# PCB_DYBoard_Transducer_CAN_ADS1113_V1.net
KiCad netlist of a schematic drawn in Altium Designer
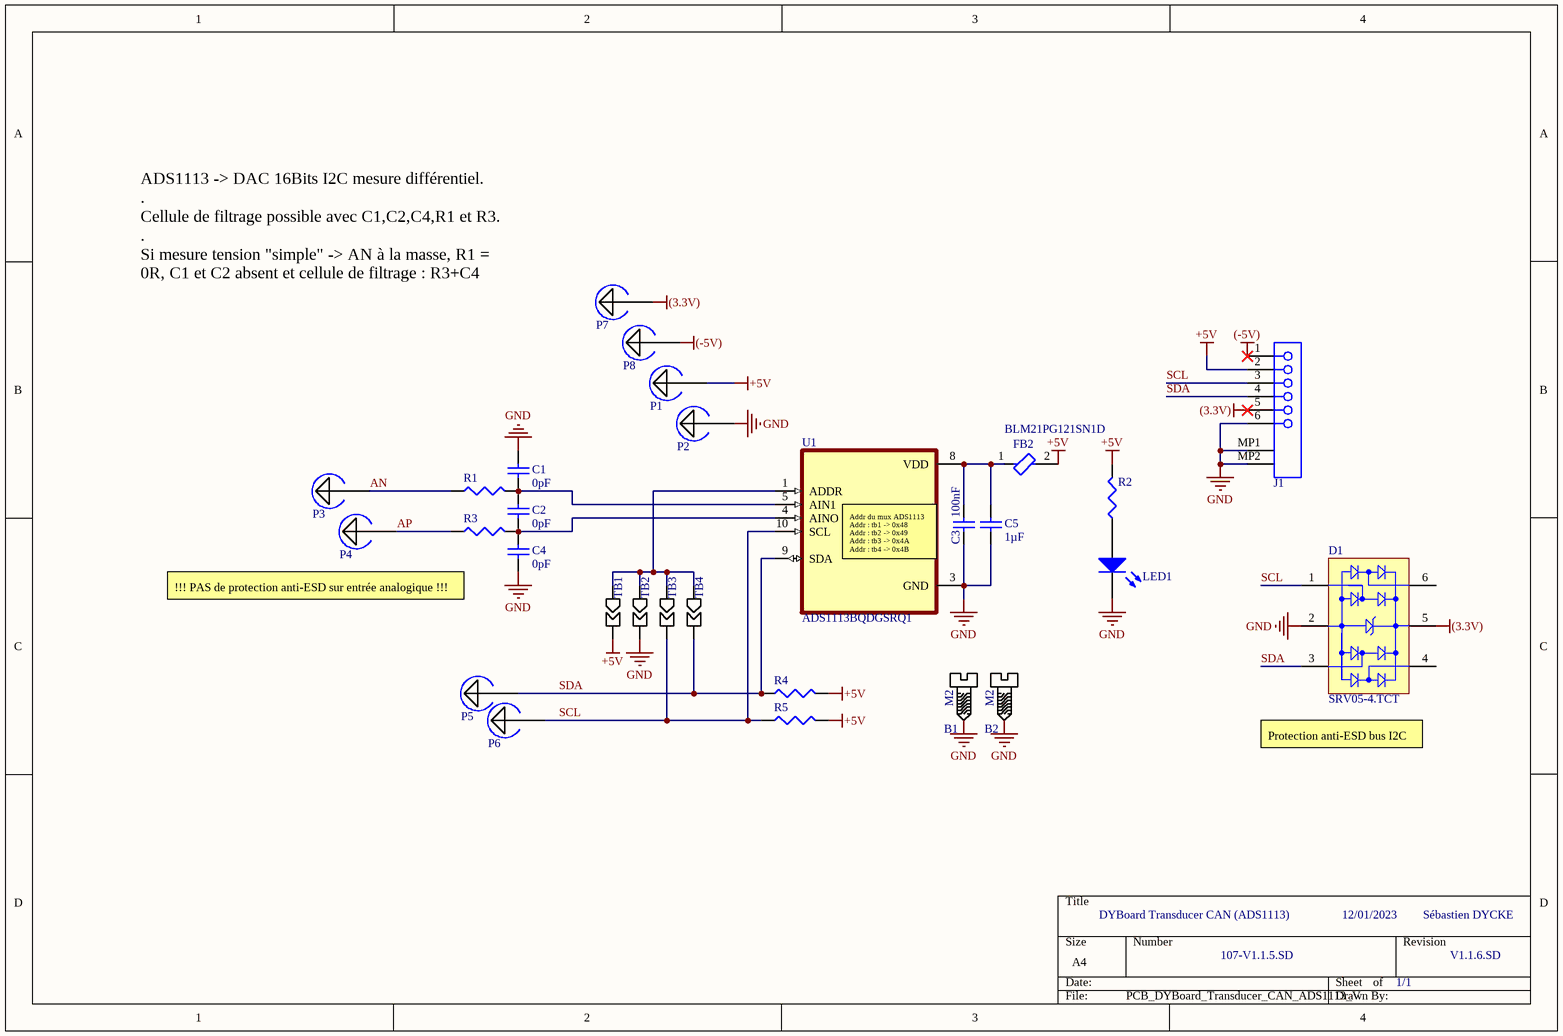
[diagram p0: PCB_DYBoard_Transducer_CAN_ADS1113_V1.SchDoc]

(export (version "E")
  (design (tool "Eeschema 10.0.6"))
  (components
    (comp (ref "B1")
      (value "bolt_M2")
      (footprint "bolt_M2")
      (libsource (lib "Lib_Altium_Sebastien_DYCKE") (part "bolt_M2"))
    )
    (comp (ref "B2")
      (value "bolt_M2")
      (footprint "bolt_M2")
      (libsource (lib "Lib_Altium_Sebastien_DYCKE") (part "bolt_M2"))
    )
    (comp (ref "C1")
      (value "0pF")
      (footprint "1608[0603]")
      (description "Capacitor (Semiconductor SIM Model)")
      (fields (field (name "Comment") "Cap Semi") (field (name "PUBLISHER") "Altium Limited"))
      (libsource (lib "Miscellaneous Devices") (part "Cap Semi"))
    )
    (comp (ref "C2")
      (value "0pF")
      (footprint "1608[0603]")
      (description "Capacitor (Semiconductor SIM Model)")
      (fields (field (name "Comment") "Cap Semi") (field (name "PUBLISHER") "Altium Limited"))
      (libsource (lib "Miscellaneous Devices") (part "Cap Semi"))
    )
    (comp (ref "C3")
      (value "100nF")
      (footprint "1608[0603]")
      (description "Capacitor (Semiconductor SIM Model)")
      (fields (field (name "Comment") "Cap Semi") (field (name "PUBLISHER") "Altium Limited"))
      (libsource (lib "Miscellaneous Devices") (part "Cap Semi"))
    )
    (comp (ref "C4")
      (value "0pF")
      (footprint "1608[0603]")
      (description "Capacitor (Semiconductor SIM Model)")
      (fields (field (name "Comment") "Cap Semi") (field (name "PUBLISHER") "Altium Limited"))
      (libsource (lib "Miscellaneous Devices") (part "Cap Semi"))
    )
    (comp (ref "C5")
      (value "1µF")
      (footprint "1608[0603]")
      (description "Capacitor (Semiconductor SIM Model)")
      (fields (field (name "Comment") "Cap Semi") (field (name "PUBLISHER") "Altium Limited"))
      (libsource (lib "Miscellaneous Devices") (part "Cap Semi"))
    )
    (comp (ref "D1")
      (value "SRV05-4.TCT")
      (footprint "SMTC-SOT23-6_V")
      (fields (field (name "MANUFACTURER") "Semtech"))
      (libsource (lib "Altium Content Vault") (part "STM-USB_DVI_HDMIULC6-4SC6X-SOT23-6L"))
    )
    (comp (ref "FB2")
      (value "BLM21PG121SN1D")
      (footprint "FP-BLM21-0_2-t0_85-e0_5-d-IPC_C")
      (description "Chip Ferrite Bead, 0805, 120Ω @ 100MHz, 0.03Ω, 25%, 3A")
      (fields (field (name "TOLERANCE") "25%"))
      (libsource (lib "Altium Content Vault") (part "5f30dd21d616792df468990f7003faa"))
    )
    (comp (ref "J1")
      (value "SEB_MOLeX_6p")
      (footprint "SEB_MOLeX_6p")
      (libsource (lib "Lib_Altium_Sebastien_DYCKE") (part "SEB_MOLeX_6p"))
    )
    (comp (ref "LED1")
      (value "150060BS75000")
      (footprint "0603_A")
      (description "SMD mono-color Chip LED, WL-SMCW, Blue")
      (fields (field (name "MANUFACTURER") "Wuerth Elektronik"))
      (libsource (lib "Altium Content Vault") (part "WE-LED_K1A2-2"))
    )
    (comp (ref "P1")
      (value "solderPad")
      (footprint "solderPad_2")
      (libsource (lib "Lib_Altium_Sebastien_DYCKE") (part "solderPad"))
    )
    (comp (ref "P2")
      (value "solderPad")
      (footprint "solderPad_2")
      (libsource (lib "Lib_Altium_Sebastien_DYCKE") (part "solderPad"))
    )
    (comp (ref "P3")
      (value "solderPad")
      (footprint "solderPad_2")
      (libsource (lib "Lib_Altium_Sebastien_DYCKE") (part "solderPad"))
    )
    (comp (ref "P4")
      (value "solderPad")
      (footprint "solderPad_2")
      (libsource (lib "Lib_Altium_Sebastien_DYCKE") (part "solderPad"))
    )
    (comp (ref "P5")
      (value "solderPad")
      (footprint "solderPad_2")
      (libsource (lib "Lib_Altium_Sebastien_DYCKE") (part "solderPad"))
    )
    (comp (ref "P6")
      (value "solderPad")
      (footprint "solderPad_2")
      (libsource (lib "Lib_Altium_Sebastien_DYCKE") (part "solderPad"))
    )
    (comp (ref "P7")
      (value "solderPad")
      (footprint "solderPad_2")
      (libsource (lib "Lib_Altium_Sebastien_DYCKE") (part "solderPad"))
    )
    (comp (ref "P8")
      (value "solderPad")
      (footprint "solderPad_2")
      (libsource (lib "Lib_Altium_Sebastien_DYCKE") (part "solderPad"))
    )
    (comp (ref "R1")
      (value "Res3")
      (footprint "J1-0603")
      (description "Resistor")
      (fields (field (name "PUBLISHER") "Altium Limited"))
      (libsource (lib "Miscellaneous Devices") (part "Res3"))
    )
    (comp (ref "R2")
      (value "Res3")
      (footprint "J1-0603")
      (description "Resistor")
      (fields (field (name "PUBLISHER") "Altium Limited"))
      (libsource (lib "Miscellaneous Devices") (part "Res3"))
    )
    (comp (ref "R3")
      (value "Res3")
      (footprint "J1-0603")
      (description "Resistor")
      (fields (field (name "PUBLISHER") "Altium Limited"))
      (libsource (lib "Miscellaneous Devices") (part "Res3"))
    )
    (comp (ref "R4")
      (value "Res3")
      (footprint "J1-0603")
      (description "Resistor")
      (fields (field (name "PUBLISHER") "Altium Limited"))
      (libsource (lib "Miscellaneous Devices") (part "Res3"))
    )
    (comp (ref "R5")
      (value "Res3")
      (footprint "J1-0603")
      (description "Resistor")
      (fields (field (name "PUBLISHER") "Altium Limited"))
      (libsource (lib "Miscellaneous Devices") (part "Res3"))
    )
    (comp (ref "TB1")
      (value "tin_bridge")
      (footprint "tin_bridge")
      (libsource (lib "Lib_Altium_Sebastien_DYCKE") (part "tin_bridge"))
    )
    (comp (ref "TB2")
      (value "tin_bridge")
      (footprint "tin_bridge")
      (libsource (lib "Lib_Altium_Sebastien_DYCKE") (part "tin_bridge"))
    )
    (comp (ref "TB3")
      (value "tin_bridge")
      (footprint "tin_bridge")
      (libsource (lib "Lib_Altium_Sebastien_DYCKE") (part "tin_bridge"))
    )
    (comp (ref "TB4")
      (value "tin_bridge")
      (footprint "tin_bridge")
      (libsource (lib "Lib_Altium_Sebastien_DYCKE") (part "tin_bridge"))
    )
    (comp (ref "U1")
      (value "ADS1113BQDGSRQ1")
      (footprint "SOP50P490X110-10N")
      (libsource (lib "ADS1113BQDGSRQ1") (part "ADS1113BQDGSRQ1"))
    )
  )
  (nets
    (net (code "1") (name "(-5V)") (class "Default")
      (node (ref "J1") (pin "1") (pinfunction "1_1") (pintype "passive"))
      (node (ref "P8") (pin "20") (pinfunction "20_20") (pintype "passive"))
    )
    (net (code "2") (name "(3.3V)") (class "Default")
      (node (ref "D1") (pin "5") (pinfunction "VBUS_5") (pintype "passive"))
      (node (ref "J1") (pin "5") (pinfunction "5_5") (pintype "passive"))
      (node (ref "P7") (pin "20") (pinfunction "20_20") (pintype "passive"))
    )
    (net (code "3") (name "+5V") (class "Default")
      (node (ref "FB2") (pin "2") (pinfunction "2_2") (pintype "passive"))
      (node (ref "J1") (pin "2") (pinfunction "2_2") (pintype "passive"))
      (node (ref "P1") (pin "20") (pinfunction "20_20") (pintype "passive"))
      (node (ref "R2") (pin "2") (pinfunction "2_2") (pintype "passive"))
      (node (ref "R4") (pin "2") (pinfunction "2_2") (pintype "passive"))
      (node (ref "R5") (pin "2") (pinfunction "2_2") (pintype "passive"))
      (node (ref "TB1") (pin "22") (pinfunction "22_22") (pintype "passive"))
    )
    (net (code "4") (name "/AN") (class "Default")
      (node (ref "P3") (pin "20") (pinfunction "20_20") (pintype "passive"))
      (node (ref "R1") (pin "1") (pinfunction "1_1") (pintype "passive"))
    )
    (net (code "5") (name "/AP") (class "Default")
      (node (ref "P4") (pin "20") (pinfunction "20_20") (pintype "passive"))
      (node (ref "R3") (pin "1") (pinfunction "1_1") (pintype "passive"))
    )
    (net (code "6") (name "/SCL") (class "Default")
      (node (ref "D1") (pin "1") (pinfunction "I/O_1_1") (pintype "passive"))
      (node (ref "J1") (pin "3") (pinfunction "3_3") (pintype "passive"))
      (node (ref "P6") (pin "20") (pinfunction "20_20") (pintype "passive"))
      (node (ref "R5") (pin "1") (pinfunction "1_1") (pintype "passive"))
      (node (ref "TB3") (pin "22") (pinfunction "22_22") (pintype "passive"))
      (node (ref "U1") (pin "10") (pinfunction "SCL_10") (pintype "input"))
    )
    (net (code "7") (name "/SDA") (class "Default")
      (node (ref "D1") (pin "3") (pinfunction "I/O_2_3") (pintype "passive"))
      (node (ref "J1") (pin "4") (pinfunction "4_4") (pintype "passive"))
      (node (ref "P5") (pin "20") (pinfunction "20_20") (pintype "passive"))
      (node (ref "R4") (pin "1") (pinfunction "1_1") (pintype "passive"))
      (node (ref "TB4") (pin "22") (pinfunction "22_22") (pintype "passive"))
      (node (ref "U1") (pin "9") (pinfunction "SDA_9") (pintype "bidirectional"))
    )
    (net (code "8") (name "GND") (class "Default")
      (node (ref "B1") (pin "20") (pinfunction "20_20") (pintype "passive"))
      (node (ref "B2") (pin "20") (pinfunction "20_20") (pintype "passive"))
      (node (ref "C1") (pin "2") (pinfunction "2_2") (pintype "passive"))
      (node (ref "C3") (pin "1") (pinfunction "1_1") (pintype "passive"))
      (node (ref "C4") (pin "1") (pinfunction "1_1") (pintype "passive"))
      (node (ref "C5") (pin "1") (pinfunction "1_1") (pintype "passive"))
      (node (ref "D1") (pin "2") (pinfunction "GND_2") (pintype "passive"))
      (node (ref "J1") (pin "6") (pinfunction "6_6") (pintype "passive"))
      (node (ref "J1") (pin "MP1") (pinfunction "MP1_MP1") (pintype "passive"))
      (node (ref "J1") (pin "MP2") (pinfunction "MP2_MP2") (pintype "passive"))
      (node (ref "LED1") (pin "1") (pinfunction "K_1") (pintype "passive"))
      (node (ref "P2") (pin "20") (pinfunction "20_20") (pintype "passive"))
      (node (ref "TB2") (pin "22") (pinfunction "22_22") (pintype "passive"))
      (node (ref "U1") (pin "3") (pinfunction "GND_3") (pintype "power_in"))
    )
    (net (code "9") (name "Net-(LED1-A)") (class "Default")
      (node (ref "LED1") (pin "2") (pinfunction "A_2") (pintype "passive"))
      (node (ref "R2") (pin "1") (pinfunction "1_1") (pintype "passive"))
    )
    (net (code "10") (name "Net-(U1-ADDR)") (class "Default")
      (node (ref "TB1") (pin "21") (pinfunction "21_21") (pintype "passive"))
      (node (ref "TB2") (pin "21") (pinfunction "21_21") (pintype "passive"))
      (node (ref "TB3") (pin "21") (pinfunction "21_21") (pintype "passive"))
      (node (ref "TB4") (pin "21") (pinfunction "21_21") (pintype "passive"))
      (node (ref "U1") (pin "1") (pinfunction "ADDR_1") (pintype "input"))
    )
    (net (code "11") (name "Net-(U1-AIN1)") (class "Default")
      (node (ref "C1") (pin "1") (pinfunction "1_1") (pintype "passive"))
      (node (ref "C2") (pin "2") (pinfunction "2_2") (pintype "passive"))
      (node (ref "R1") (pin "2") (pinfunction "2_2") (pintype "passive"))
      (node (ref "U1") (pin "5") (pinfunction "AIN1_5") (pintype "input"))
    )
    (net (code "12") (name "Net-(U1-AINO)") (class "Default")
      (node (ref "C2") (pin "1") (pinfunction "1_1") (pintype "passive"))
      (node (ref "C4") (pin "2") (pinfunction "2_2") (pintype "passive"))
      (node (ref "R3") (pin "2") (pinfunction "2_2") (pintype "passive"))
      (node (ref "U1") (pin "4") (pinfunction "AINO_4") (pintype "input"))
    )
    (net (code "13") (name "Net-(U1-VDD)") (class "Default")
      (node (ref "C3") (pin "2") (pinfunction "2_2") (pintype "passive"))
      (node (ref "C5") (pin "2") (pinfunction "2_2") (pintype "passive"))
      (node (ref "FB2") (pin "1") (pinfunction "1_1") (pintype "passive"))
      (node (ref "U1") (pin "8") (pinfunction "VDD_8") (pintype "power_in"))
    )
    (net (code "14") (name "unconnected-(D1-I{slash}O_3-Pad4)") (class "Default")
      (node (ref "D1") (pin "4") (pinfunction "I/O_3_4") (pintype "passive"))
    )
    (net (code "15") (name "unconnected-(D1-I{slash}O_4-Pad6)") (class "Default")
      (node (ref "D1") (pin "6") (pinfunction "I/O_4_6") (pintype "passive"))
    )
  )
)
